# PCM2707_DAC.net
KiCad netlist of a schematic drawn in EAGLE
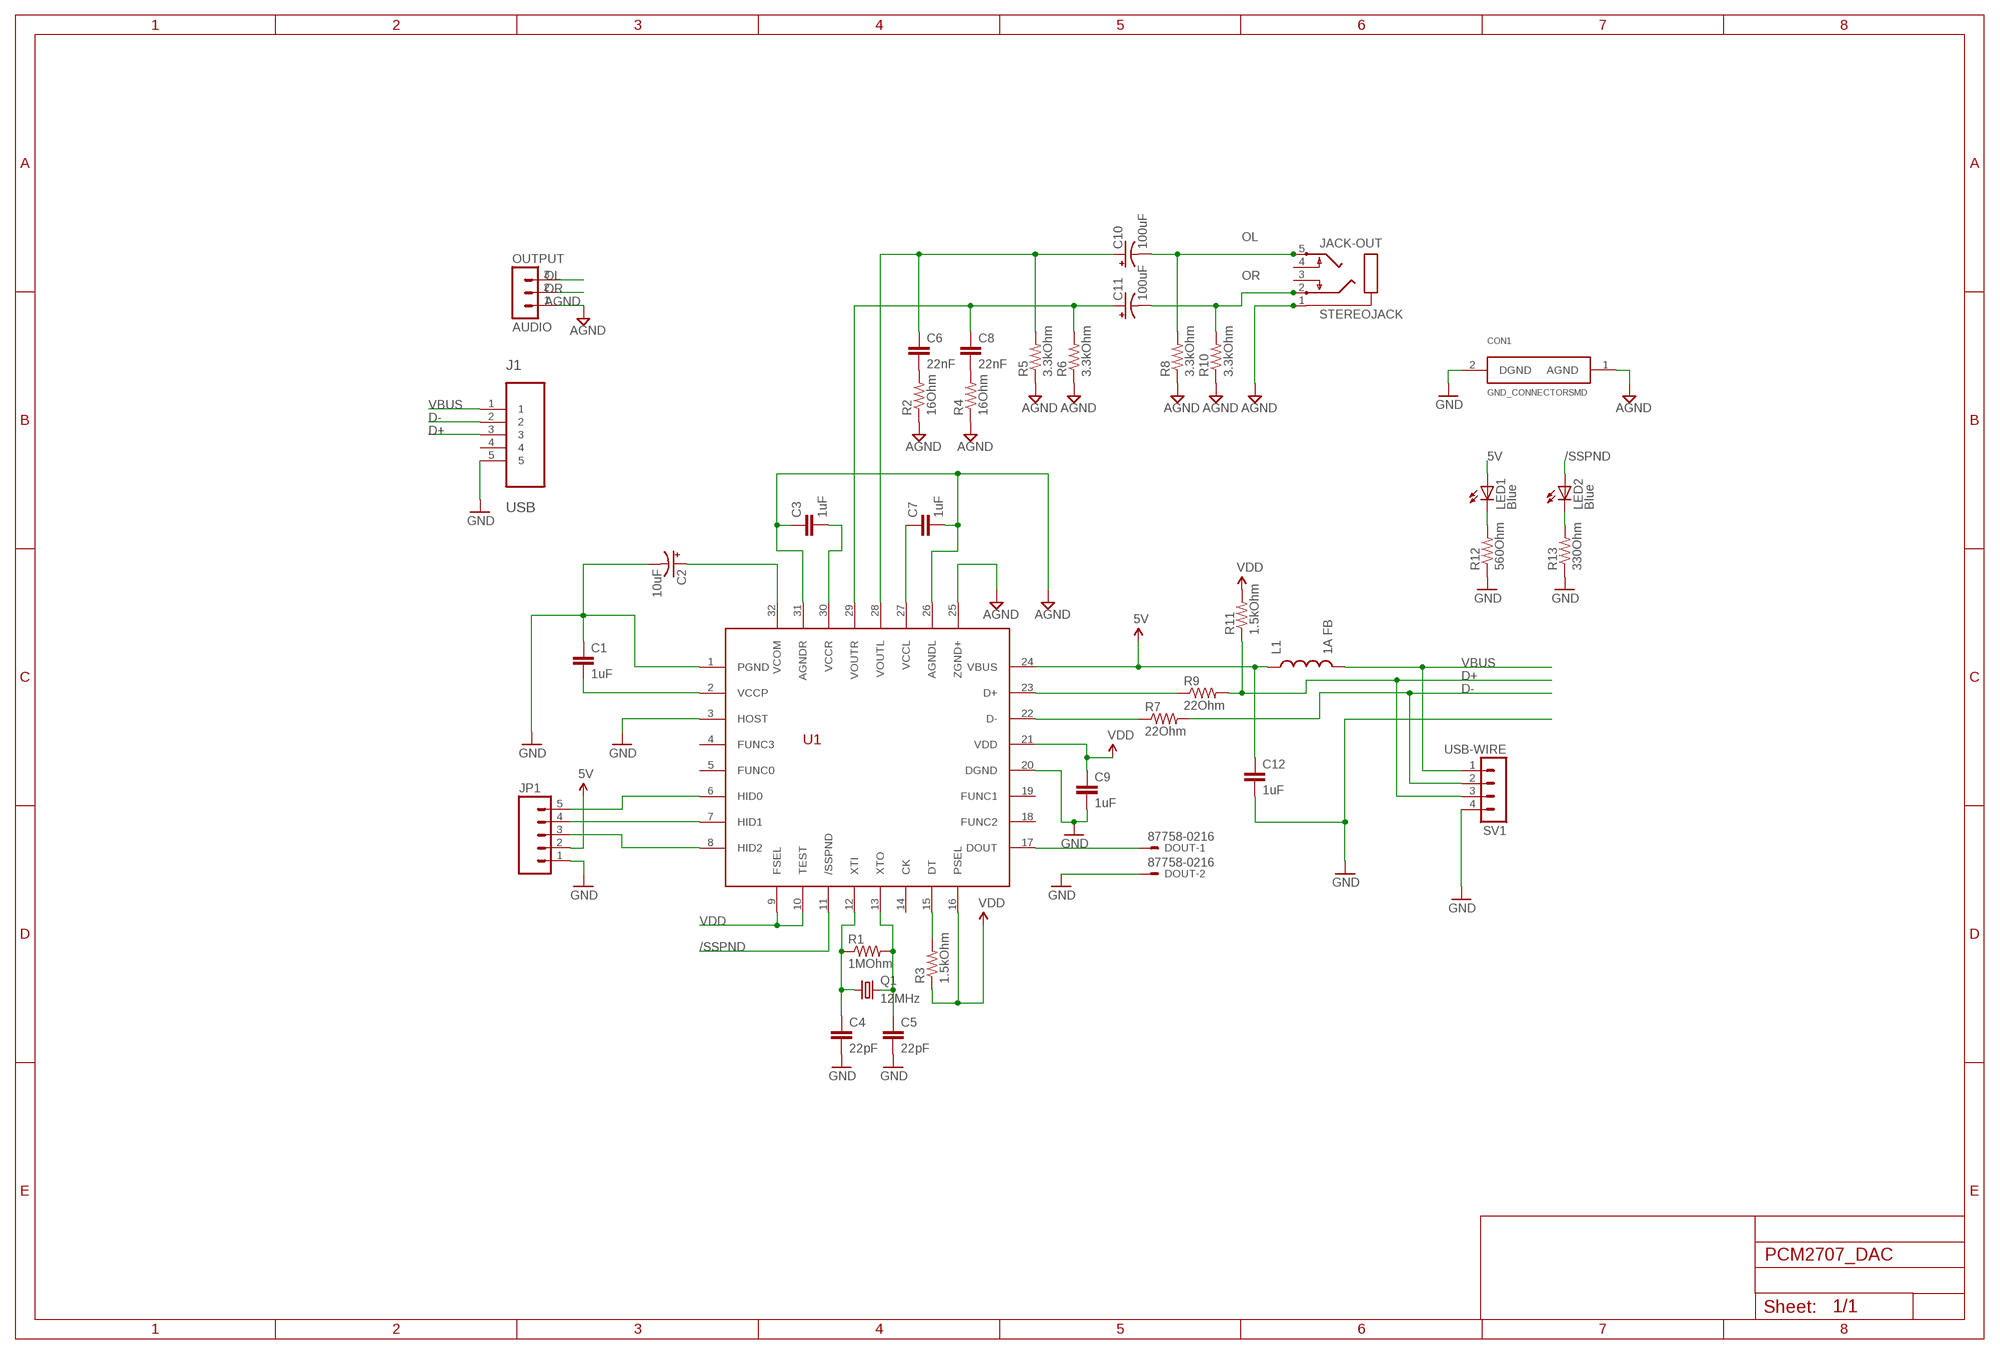
[diagram p0: schematic, sheet 1]

(export (version "E")
  (design (tool "Eeschema 10.0.6"))
  (components
    (comp (ref "C1")
      (value "1uF")
      (footprint "eagle-import:0805")
      (libsource (lib "eagle-import") (part "CAP0805"))
    )
    (comp (ref "C2")
      (value "10uF")
      (footprint "eagle-import:PANASONIC_C")
      (libsource (lib "eagle-import") (part "CAP_POLC"))
    )
    (comp (ref "C3")
      (value "1uF")
      (footprint "eagle-import:0805")
      (libsource (lib "eagle-import") (part "CAP0805"))
    )
    (comp (ref "C4")
      (value "22pF")
      (footprint "eagle-import:0805")
      (libsource (lib "eagle-import") (part "CAP0805"))
    )
    (comp (ref "C5")
      (value "22pF")
      (footprint "eagle-import:0805")
      (libsource (lib "eagle-import") (part "CAP0805"))
    )
    (comp (ref "C6")
      (value "22nF")
      (footprint "eagle-import:1210")
      (libsource (lib "eagle-import") (part "CAP1210"))
    )
    (comp (ref "C7")
      (value "1uF")
      (footprint "eagle-import:0805")
      (libsource (lib "eagle-import") (part "CAP0805"))
    )
    (comp (ref "C8")
      (value "22nF")
      (footprint "eagle-import:1210")
      (libsource (lib "eagle-import") (part "CAP1210"))
    )
    (comp (ref "C9")
      (value "1uF")
      (footprint "eagle-import:0805")
      (libsource (lib "eagle-import") (part "CAP0805"))
    )
    (comp (ref "C10")
      (value "100uF")
      (footprint "eagle-import:PANASONIC_D")
      (libsource (lib "eagle-import") (part "CAP_POLD"))
    )
    (comp (ref "C11")
      (value "100uF")
      (footprint "eagle-import:PANASONIC_D")
      (libsource (lib "eagle-import") (part "CAP_POLD"))
    )
    (comp (ref "C12")
      (value "1uF")
      (footprint "eagle-import:0805")
      (libsource (lib "eagle-import") (part "CAP0805"))
    )
    (comp (ref "CON1")
      (value "GND_CONNECTORSMD")
      (footprint "eagle-import:GND_CONNECTOR")
      (libsource (lib "eagle-import") (part "GND_CONNECTORSMD"))
    )
    (comp (ref "DOUT")
      (value "87758-0216")
      (footprint "eagle-import:87758-0216")
      (libsource (lib "eagle-import") (part "87758-0216"))
    )
    (comp (ref "J1")
      (value "USB")
      (footprint "eagle-import:MOLEX_47346-0001")
      (fields (field (name "MPN") "47346-0001"))
      (libsource (lib "eagle-import") (part "47346-0001"))
    )
    (comp (ref "JACK-OUT")
      (value "STEREOJACK")
      (footprint "eagle-import:STX3100")
      (libsource (lib "eagle-import") (part "STEREOJACK"))
    )
    (comp (ref "JP1")
      (value "M05LOCK")
      (footprint "eagle-import:1X05_LOCK")
      (libsource (lib "eagle-import") (part "M05LOCK"))
    )
    (comp (ref "L1")
      (value "1A FB")
      (footprint "eagle-import:0805")
      (libsource (lib "eagle-import") (part "INDUCTOR0805"))
    )
    (comp (ref "LED1")
      (value "Blue")
      (footprint "eagle-import:LED-0603")
      (libsource (lib "eagle-import") (part "LED0603"))
    )
    (comp (ref "LED2")
      (value "Blue")
      (footprint "eagle-import:LED-0603")
      (libsource (lib "eagle-import") (part "LED0603"))
    )
    (comp (ref "OUTPUT")
      (value "AUDIO")
      (footprint "eagle-import:MA03-1")
      (libsource (lib "eagle-import") (part "MA03-1"))
    )
    (comp (ref "Q1")
      (value "12MHz")
      (footprint "eagle-import:HC49U-V")
      (libsource (lib "eagle-import") (part "CRYSTALHC49U-V"))
    )
    (comp (ref "R1")
      (value "1MOhm")
      (footprint "eagle-import:0805")
      (libsource (lib "eagle-import") (part "RESISTOR0805-RES"))
    )
    (comp (ref "R2")
      (value "16Ohm")
      (footprint "eagle-import:0805")
      (libsource (lib "eagle-import") (part "RESISTOR0805-RES"))
    )
    (comp (ref "R3")
      (value "1.5kOhm")
      (footprint "eagle-import:0805")
      (libsource (lib "eagle-import") (part "RESISTOR0805-RES"))
    )
    (comp (ref "R4")
      (value "16Ohm")
      (footprint "eagle-import:0805")
      (libsource (lib "eagle-import") (part "RESISTOR0805-RES"))
    )
    (comp (ref "R5")
      (value "3.3kOhm")
      (footprint "eagle-import:0805")
      (libsource (lib "eagle-import") (part "RESISTOR0805-RES"))
    )
    (comp (ref "R6")
      (value "3.3kOhm")
      (footprint "eagle-import:0805")
      (libsource (lib "eagle-import") (part "RESISTOR0805-RES"))
    )
    (comp (ref "R7")
      (value "22Ohm")
      (footprint "eagle-import:0805")
      (libsource (lib "eagle-import") (part "RESISTOR0805-RES"))
    )
    (comp (ref "R8")
      (value "3.3kOhm")
      (footprint "eagle-import:0805")
      (libsource (lib "eagle-import") (part "RESISTOR0805-RES"))
    )
    (comp (ref "R9")
      (value "22Ohm")
      (footprint "eagle-import:0805")
      (libsource (lib "eagle-import") (part "RESISTOR0805-RES"))
    )
    (comp (ref "R10")
      (value "3.3kOhm")
      (footprint "eagle-import:0805")
      (libsource (lib "eagle-import") (part "RESISTOR0805-RES"))
    )
    (comp (ref "R11")
      (value "1.5kOhm")
      (footprint "eagle-import:0805")
      (libsource (lib "eagle-import") (part "RESISTOR0805-RES"))
    )
    (comp (ref "R12")
      (value "560Ohm")
      (footprint "eagle-import:0805")
      (libsource (lib "eagle-import") (part "RESISTOR0805-RES"))
    )
    (comp (ref "R13")
      (value "330Ohm")
      (footprint "eagle-import:0805")
      (libsource (lib "eagle-import") (part "RESISTOR0805-RES"))
    )
    (comp (ref "SV1")
      (value "USB-WIRE")
      (footprint "eagle-import:MA04-1")
      (libsource (lib "eagle-import") (part "MA04-1"))
    )
    (comp (ref "U1")
      (value "PCM2707C_TQFP32\"")
      (footprint "eagle-import:32TQFP_PCM2707C")
      (libsource (lib "eagle-import") (part "PCM2707C_TQFP32{dblquote}"))
    )
  )
  (nets
    (net (code "1") (name "/D+") (class "Default")
      (node (ref "J1") (pin "3") (pinfunction "3_3") (pintype "input"))
      (node (ref "R11") (pin "1") (pinfunction "1_1") (pintype "passive"))
      (node (ref "R9") (pin "2") (pinfunction "2_2") (pintype "passive"))
      (node (ref "SV1") (pin "3") (pinfunction "3_3") (pintype "passive"))
    )
    (net (code "2") (name "/D-") (class "Default")
      (node (ref "J1") (pin "2") (pinfunction "2_2") (pintype "input"))
      (node (ref "R7") (pin "2") (pinfunction "2_2") (pintype "passive"))
      (node (ref "SV1") (pin "2") (pinfunction "2_2") (pintype "passive"))
    )
    (net (code "3") (name "/OL") (class "Default")
      (node (ref "C10") (pin "-") (pinfunction "-_-") (pintype "passive"))
      (node (ref "JACK-OUT") (pin "5") (pinfunction "5_5") (pintype "passive"))
      (node (ref "OUTPUT") (pin "3") (pinfunction "3_3") (pintype "passive"))
      (node (ref "R8") (pin "2") (pinfunction "2_2") (pintype "passive"))
    )
    (net (code "4") (name "/OR") (class "Default")
      (node (ref "C11") (pin "-") (pinfunction "-_-") (pintype "passive"))
      (node (ref "JACK-OUT") (pin "2") (pinfunction "2_2") (pintype "passive"))
      (node (ref "OUTPUT") (pin "2") (pinfunction "2_2") (pintype "passive"))
      (node (ref "R10") (pin "2") (pinfunction "2_2") (pintype "passive"))
    )
    (net (code "5") (name "/VBUS") (class "Default")
      (node (ref "J1") (pin "1") (pinfunction "1_1") (pintype "input"))
      (node (ref "L1") (pin "2") (pinfunction "2_2") (pintype "passive"))
      (node (ref "SV1") (pin "1") (pinfunction "1_1") (pintype "passive"))
    )
    (net (code "6") (name "/{slash}SSPND") (class "Default")
      (node (ref "LED2") (pin "A") (pinfunction "A_A") (pintype "passive"))
      (node (ref "U1") (pin "11") (pinfunction "/SSPND_11") (pintype "bidirectional"))
    )
    (net (code "7") (name "5V") (class "Default")
      (node (ref "C12") (pin "1") (pinfunction "1_1") (pintype "passive"))
      (node (ref "JP1") (pin "2") (pinfunction "2_2") (pintype "passive"))
      (node (ref "L1") (pin "1") (pinfunction "1_1") (pintype "passive"))
      (node (ref "LED1") (pin "A") (pinfunction "A_A") (pintype "passive"))
      (node (ref "U1") (pin "24") (pinfunction "VBUS_24") (pintype "bidirectional"))
    )
    (net (code "8") (name "AGND") (class "Default")
      (node (ref "C3") (pin "1") (pinfunction "1_1") (pintype "passive"))
      (node (ref "C7") (pin "2") (pinfunction "2_2") (pintype "passive"))
      (node (ref "CON1") (pin "1") (pinfunction "AGND_1") (pintype "bidirectional"))
      (node (ref "JACK-OUT") (pin "1") (pinfunction "1_1") (pintype "passive"))
      (node (ref "OUTPUT") (pin "1") (pinfunction "1_1") (pintype "passive"))
      (node (ref "R10") (pin "1") (pinfunction "1_1") (pintype "passive"))
      (node (ref "R2") (pin "1") (pinfunction "1_1") (pintype "passive"))
      (node (ref "R4") (pin "1") (pinfunction "1_1") (pintype "passive"))
      (node (ref "R5") (pin "1") (pinfunction "1_1") (pintype "passive"))
      (node (ref "R6") (pin "1") (pinfunction "1_1") (pintype "passive"))
      (node (ref "R8") (pin "1") (pinfunction "1_1") (pintype "passive"))
      (node (ref "U1") (pin "25") (pinfunction "ZGND+_25") (pintype "bidirectional"))
      (node (ref "U1") (pin "26") (pinfunction "AGNDL_26") (pintype "bidirectional"))
      (node (ref "U1") (pin "31") (pinfunction "AGNDR_31") (pintype "bidirectional"))
    )
    (net (code "9") (name "GND") (class "Default")
      (node (ref "C1") (pin "1") (pinfunction "1_1") (pintype "passive"))
      (node (ref "C12") (pin "2") (pinfunction "2_2") (pintype "passive"))
      (node (ref "C2") (pin "-") (pinfunction "-_-") (pintype "passive"))
      (node (ref "C4") (pin "2") (pinfunction "2_2") (pintype "passive"))
      (node (ref "C5") (pin "2") (pinfunction "2_2") (pintype "passive"))
      (node (ref "C9") (pin "2") (pinfunction "2_2") (pintype "passive"))
      (node (ref "CON1") (pin "2") (pinfunction "DGND_2") (pintype "bidirectional"))
      (node (ref "DOUT") (pin "2") (pinfunction "S_2") (pintype "passive"))
      (node (ref "J1") (pin "5") (pinfunction "5_5") (pintype "input"))
      (node (ref "JP1") (pin "1") (pinfunction "1_1") (pintype "passive"))
      (node (ref "R12") (pin "1") (pinfunction "1_1") (pintype "passive"))
      (node (ref "R13") (pin "1") (pinfunction "1_1") (pintype "passive"))
      (node (ref "SV1") (pin "4") (pinfunction "4_4") (pintype "passive"))
      (node (ref "U1") (pin "1") (pinfunction "PGND_1") (pintype "bidirectional"))
      (node (ref "U1") (pin "20") (pinfunction "DGND_20") (pintype "bidirectional"))
      (node (ref "U1") (pin "3") (pinfunction "HOST_3") (pintype "bidirectional"))
    )
    (net (code "10") (name "Net-(C6-Pad2)") (class "Default")
      (node (ref "C6") (pin "2") (pinfunction "2_2") (pintype "passive"))
      (node (ref "R2") (pin "2") (pinfunction "2_2") (pintype "passive"))
    )
    (net (code "11") (name "Net-(C8-Pad2)") (class "Default")
      (node (ref "C8") (pin "2") (pinfunction "2_2") (pintype "passive"))
      (node (ref "R4") (pin "2") (pinfunction "2_2") (pintype "passive"))
    )
    (net (code "12") (name "Net-(DOUTA-S)") (class "Default")
      (node (ref "DOUT") (pin "1") (pinfunction "S_1") (pintype "passive"))
      (node (ref "U1") (pin "17") (pinfunction "DOUT_17") (pintype "bidirectional"))
    )
    (net (code "13") (name "Net-(LED1-PadC)") (class "Default")
      (node (ref "LED1") (pin "C") (pinfunction "C_C") (pintype "passive"))
      (node (ref "R12") (pin "2") (pinfunction "2_2") (pintype "passive"))
    )
    (net (code "14") (name "Net-(LED2-PadC)") (class "Default")
      (node (ref "LED2") (pin "C") (pinfunction "C_C") (pintype "passive"))
      (node (ref "R13") (pin "2") (pinfunction "2_2") (pintype "passive"))
    )
    (net (code "15") (name "Net-(U1-D+)") (class "Default")
      (node (ref "R9") (pin "1") (pinfunction "1_1") (pintype "passive"))
      (node (ref "U1") (pin "23") (pinfunction "D+_23") (pintype "bidirectional"))
    )
    (net (code "16") (name "Net-(U1-D-)") (class "Default")
      (node (ref "R7") (pin "1") (pinfunction "1_1") (pintype "passive"))
      (node (ref "U1") (pin "22") (pinfunction "D-_22") (pintype "bidirectional"))
    )
    (net (code "17") (name "Net-(U1-DT)") (class "Default")
      (node (ref "R3") (pin "2") (pinfunction "2_2") (pintype "passive"))
      (node (ref "U1") (pin "15") (pinfunction "DT_15") (pintype "bidirectional"))
    )
    (net (code "18") (name "Net-(U1-HID0)") (class "Default")
      (node (ref "JP1") (pin "5") (pinfunction "5_5") (pintype "passive"))
      (node (ref "U1") (pin "6") (pinfunction "HID0_6") (pintype "bidirectional"))
    )
    (net (code "19") (name "Net-(U1-HID1)") (class "Default")
      (node (ref "JP1") (pin "4") (pinfunction "4_4") (pintype "passive"))
      (node (ref "U1") (pin "7") (pinfunction "HID1_7") (pintype "bidirectional"))
    )
    (net (code "20") (name "Net-(U1-HID2)") (class "Default")
      (node (ref "JP1") (pin "3") (pinfunction "3_3") (pintype "passive"))
      (node (ref "U1") (pin "8") (pinfunction "HID2_8") (pintype "bidirectional"))
    )
    (net (code "21") (name "Net-(U1-VCCL)") (class "Default")
      (node (ref "C7") (pin "1") (pinfunction "1_1") (pintype "passive"))
      (node (ref "U1") (pin "27") (pinfunction "VCCL_27") (pintype "bidirectional"))
    )
    (net (code "22") (name "Net-(U1-VCCP)") (class "Default")
      (node (ref "C1") (pin "2") (pinfunction "2_2") (pintype "passive"))
      (node (ref "U1") (pin "2") (pinfunction "VCCP_2") (pintype "bidirectional"))
    )
    (net (code "23") (name "Net-(U1-VCCR)") (class "Default")
      (node (ref "C3") (pin "2") (pinfunction "2_2") (pintype "passive"))
      (node (ref "U1") (pin "30") (pinfunction "VCCR_30") (pintype "bidirectional"))
    )
    (net (code "24") (name "Net-(U1-VCOM)") (class "Default")
      (node (ref "C2") (pin "+") (pinfunction "+_+") (pintype "passive"))
      (node (ref "U1") (pin "32") (pinfunction "VCOM_32") (pintype "bidirectional"))
    )
    (net (code "25") (name "Net-(U1-VOUTL)") (class "Default")
      (node (ref "C10") (pin "+") (pinfunction "+_+") (pintype "passive"))
      (node (ref "C6") (pin "1") (pinfunction "1_1") (pintype "passive"))
      (node (ref "R5") (pin "2") (pinfunction "2_2") (pintype "passive"))
      (node (ref "U1") (pin "28") (pinfunction "VOUTL_28") (pintype "bidirectional"))
    )
    (net (code "26") (name "Net-(U1-VOUTR)") (class "Default")
      (node (ref "C11") (pin "+") (pinfunction "+_+") (pintype "passive"))
      (node (ref "C8") (pin "1") (pinfunction "1_1") (pintype "passive"))
      (node (ref "R6") (pin "2") (pinfunction "2_2") (pintype "passive"))
      (node (ref "U1") (pin "29") (pinfunction "VOUTR_29") (pintype "bidirectional"))
    )
    (net (code "27") (name "Net-(U1-XTI)") (class "Default")
      (node (ref "C4") (pin "1") (pinfunction "1_1") (pintype "passive"))
      (node (ref "Q1") (pin "1") (pinfunction "1_1") (pintype "passive"))
      (node (ref "R1") (pin "1") (pinfunction "1_1") (pintype "passive"))
      (node (ref "U1") (pin "12") (pinfunction "XTI_12") (pintype "bidirectional"))
    )
    (net (code "28") (name "Net-(U1-XTO)") (class "Default")
      (node (ref "C5") (pin "1") (pinfunction "1_1") (pintype "passive"))
      (node (ref "Q1") (pin "2") (pinfunction "2_2") (pintype "passive"))
      (node (ref "R1") (pin "2") (pinfunction "2_2") (pintype "passive"))
      (node (ref "U1") (pin "13") (pinfunction "XTO_13") (pintype "bidirectional"))
    )
    (net (code "29") (name "VDD") (class "Default")
      (node (ref "C9") (pin "1") (pinfunction "1_1") (pintype "passive"))
      (node (ref "R11") (pin "2") (pinfunction "2_2") (pintype "passive"))
      (node (ref "R3") (pin "1") (pinfunction "1_1") (pintype "passive"))
      (node (ref "U1") (pin "10") (pinfunction "TEST_10") (pintype "bidirectional"))
      (node (ref "U1") (pin "16") (pinfunction "PSEL_16") (pintype "bidirectional"))
      (node (ref "U1") (pin "21") (pinfunction "VDD_21") (pintype "bidirectional"))
      (node (ref "U1") (pin "9") (pinfunction "FSEL_9") (pintype "bidirectional"))
    )
    (net (code "30") (name "unconnected-(J1-Pad4)") (class "Default")
      (node (ref "J1") (pin "4") (pinfunction "4_4") (pintype "input"))
    )
    (net (code "31") (name "unconnected-(JACK-OUT-Pad3)") (class "Default")
      (node (ref "JACK-OUT") (pin "3") (pinfunction "3_3") (pintype "passive"))
    )
    (net (code "32") (name "unconnected-(JACK-OUT-Pad4)") (class "Default")
      (node (ref "JACK-OUT") (pin "4") (pinfunction "4_4") (pintype "passive"))
    )
    (net (code "33") (name "unconnected-(U1-CK-Pad14)") (class "Default")
      (node (ref "U1") (pin "14") (pinfunction "CK_14") (pintype "bidirectional"))
    )
    (net (code "34") (name "unconnected-(U1-FUNC0-Pad5)") (class "Default")
      (node (ref "U1") (pin "5") (pinfunction "FUNC0_5") (pintype "bidirectional"))
    )
    (net (code "35") (name "unconnected-(U1-FUNC1-Pad19)") (class "Default")
      (node (ref "U1") (pin "19") (pinfunction "FUNC1_19") (pintype "bidirectional"))
    )
    (net (code "36") (name "unconnected-(U1-FUNC2-Pad18)") (class "Default")
      (node (ref "U1") (pin "18") (pinfunction "FUNC2_18") (pintype "bidirectional"))
    )
    (net (code "37") (name "unconnected-(U1-FUNC3-Pad4)") (class "Default")
      (node (ref "U1") (pin "4") (pinfunction "FUNC3_4") (pintype "bidirectional"))
    )
  )
)
